# serial_led_controller_programmieradapter.net
KiCad netlist of a schematic drawn in EAGLE
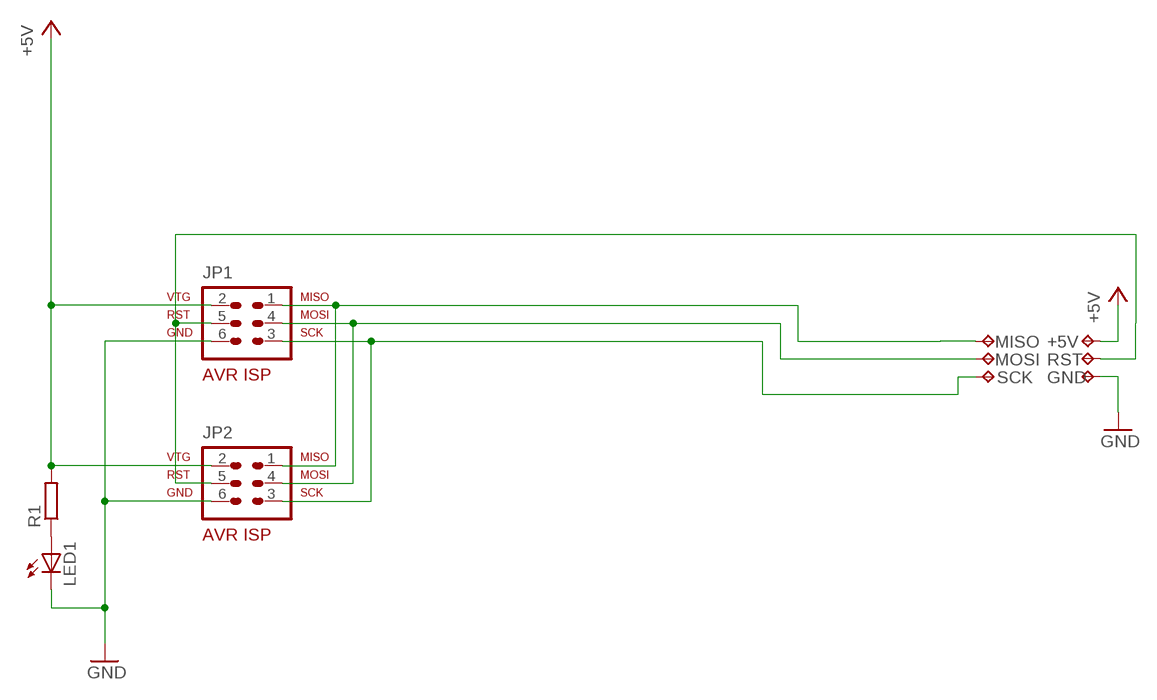
[diagram p0: schematic, sheet 1]

(export (version "E")
  (design (tool "Eeschema 10.0.6"))
  (components
    (comp (ref "+5V")
      (value "TPTP19R")
      (footprint "eagle-import:TP19R")
      (libsource (lib "eagle-import") (part "TPTP19R"))
    )
    (comp (ref "GND")
      (value "TPTP19R")
      (footprint "eagle-import:TP19R")
      (libsource (lib "eagle-import") (part "TPTP19R"))
    )
    (comp (ref "JP1")
      (value "AVR-ISP-6")
      (footprint "eagle-import:AVR-ISP-6")
      (libsource (lib "eagle-import") (part "AVR-ISP-6"))
    )
    (comp (ref "JP2")
      (value "AVR-ISP-6")
      (footprint "eagle-import:AVR-ISP-6")
      (libsource (lib "eagle-import") (part "AVR-ISP-6"))
    )
    (comp (ref "LED1")
      (value "LED3MM")
      (footprint "eagle-import:LED3MM")
      (libsource (lib "eagle-import") (part "LED3MM"))
    )
    (comp (ref "MISO")
      (value "TPTP19R")
      (footprint "eagle-import:TP19R")
      (libsource (lib "eagle-import") (part "TPTP19R"))
    )
    (comp (ref "MOSI")
      (value "TPTP19R")
      (footprint "eagle-import:TP19R")
      (libsource (lib "eagle-import") (part "TPTP19R"))
    )
    (comp (ref "R1")
      (value "R-EU_0207/10")
      (footprint "eagle-import:0207_10")
      (libsource (lib "eagle-import") (part "R-EU_0207/10"))
    )
    (comp (ref "RST")
      (value "TPTP19R")
      (footprint "eagle-import:TP19R")
      (libsource (lib "eagle-import") (part "TPTP19R"))
    )
    (comp (ref "SCK")
      (value "TPTP19R")
      (footprint "eagle-import:TP19R")
      (libsource (lib "eagle-import") (part "TPTP19R"))
    )
  )
  (nets
    (net (code "1") (name "+5V") (class "Default")
      (node (ref "+5V") (pin "TP") (pinfunction "TP_TP") (pintype "input"))
      (node (ref "JP1") (pin "2") (pinfunction "2_2") (pintype "passive"))
      (node (ref "JP2") (pin "2") (pinfunction "2_2") (pintype "passive"))
      (node (ref "R1") (pin "2") (pinfunction "2_2") (pintype "passive"))
    )
    (net (code "2") (name "GND") (class "Default")
      (node (ref "GND") (pin "TP") (pinfunction "TP_TP") (pintype "input"))
      (node (ref "JP1") (pin "6") (pinfunction "6_6") (pintype "passive"))
      (node (ref "JP2") (pin "6") (pinfunction "6_6") (pintype "passive"))
      (node (ref "LED1") (pin "K") (pinfunction "C_K") (pintype "passive"))
    )
    (net (code "3") (name "Net-(JP1-Pad1)") (class "Default")
      (node (ref "JP1") (pin "1") (pinfunction "1_1") (pintype "passive"))
      (node (ref "JP2") (pin "1") (pinfunction "1_1") (pintype "passive"))
      (node (ref "MISO") (pin "TP") (pinfunction "TP_TP") (pintype "input"))
    )
    (net (code "4") (name "Net-(JP1-Pad3)") (class "Default")
      (node (ref "JP1") (pin "3") (pinfunction "3_3") (pintype "passive"))
      (node (ref "JP2") (pin "3") (pinfunction "3_3") (pintype "passive"))
      (node (ref "SCK") (pin "TP") (pinfunction "TP_TP") (pintype "input"))
    )
    (net (code "5") (name "Net-(JP1-Pad4)") (class "Default")
      (node (ref "JP1") (pin "4") (pinfunction "4_4") (pintype "passive"))
      (node (ref "JP2") (pin "4") (pinfunction "4_4") (pintype "passive"))
      (node (ref "MOSI") (pin "TP") (pinfunction "TP_TP") (pintype "input"))
    )
    (net (code "6") (name "Net-(JP1-Pad5)") (class "Default")
      (node (ref "JP1") (pin "5") (pinfunction "5_5") (pintype "passive"))
      (node (ref "JP2") (pin "5") (pinfunction "5_5") (pintype "passive"))
      (node (ref "RST") (pin "TP") (pinfunction "TP_TP") (pintype "input"))
    )
    (net (code "7") (name "Net-(LED1-PadA)") (class "Default")
      (node (ref "LED1") (pin "A") (pinfunction "A_A") (pintype "passive"))
      (node (ref "R1") (pin "1") (pinfunction "1_1") (pintype "passive"))
    )
  )
)
